# SPEAR_Speedy.net
KiCad netlist of a schematic drawn in EAGLE
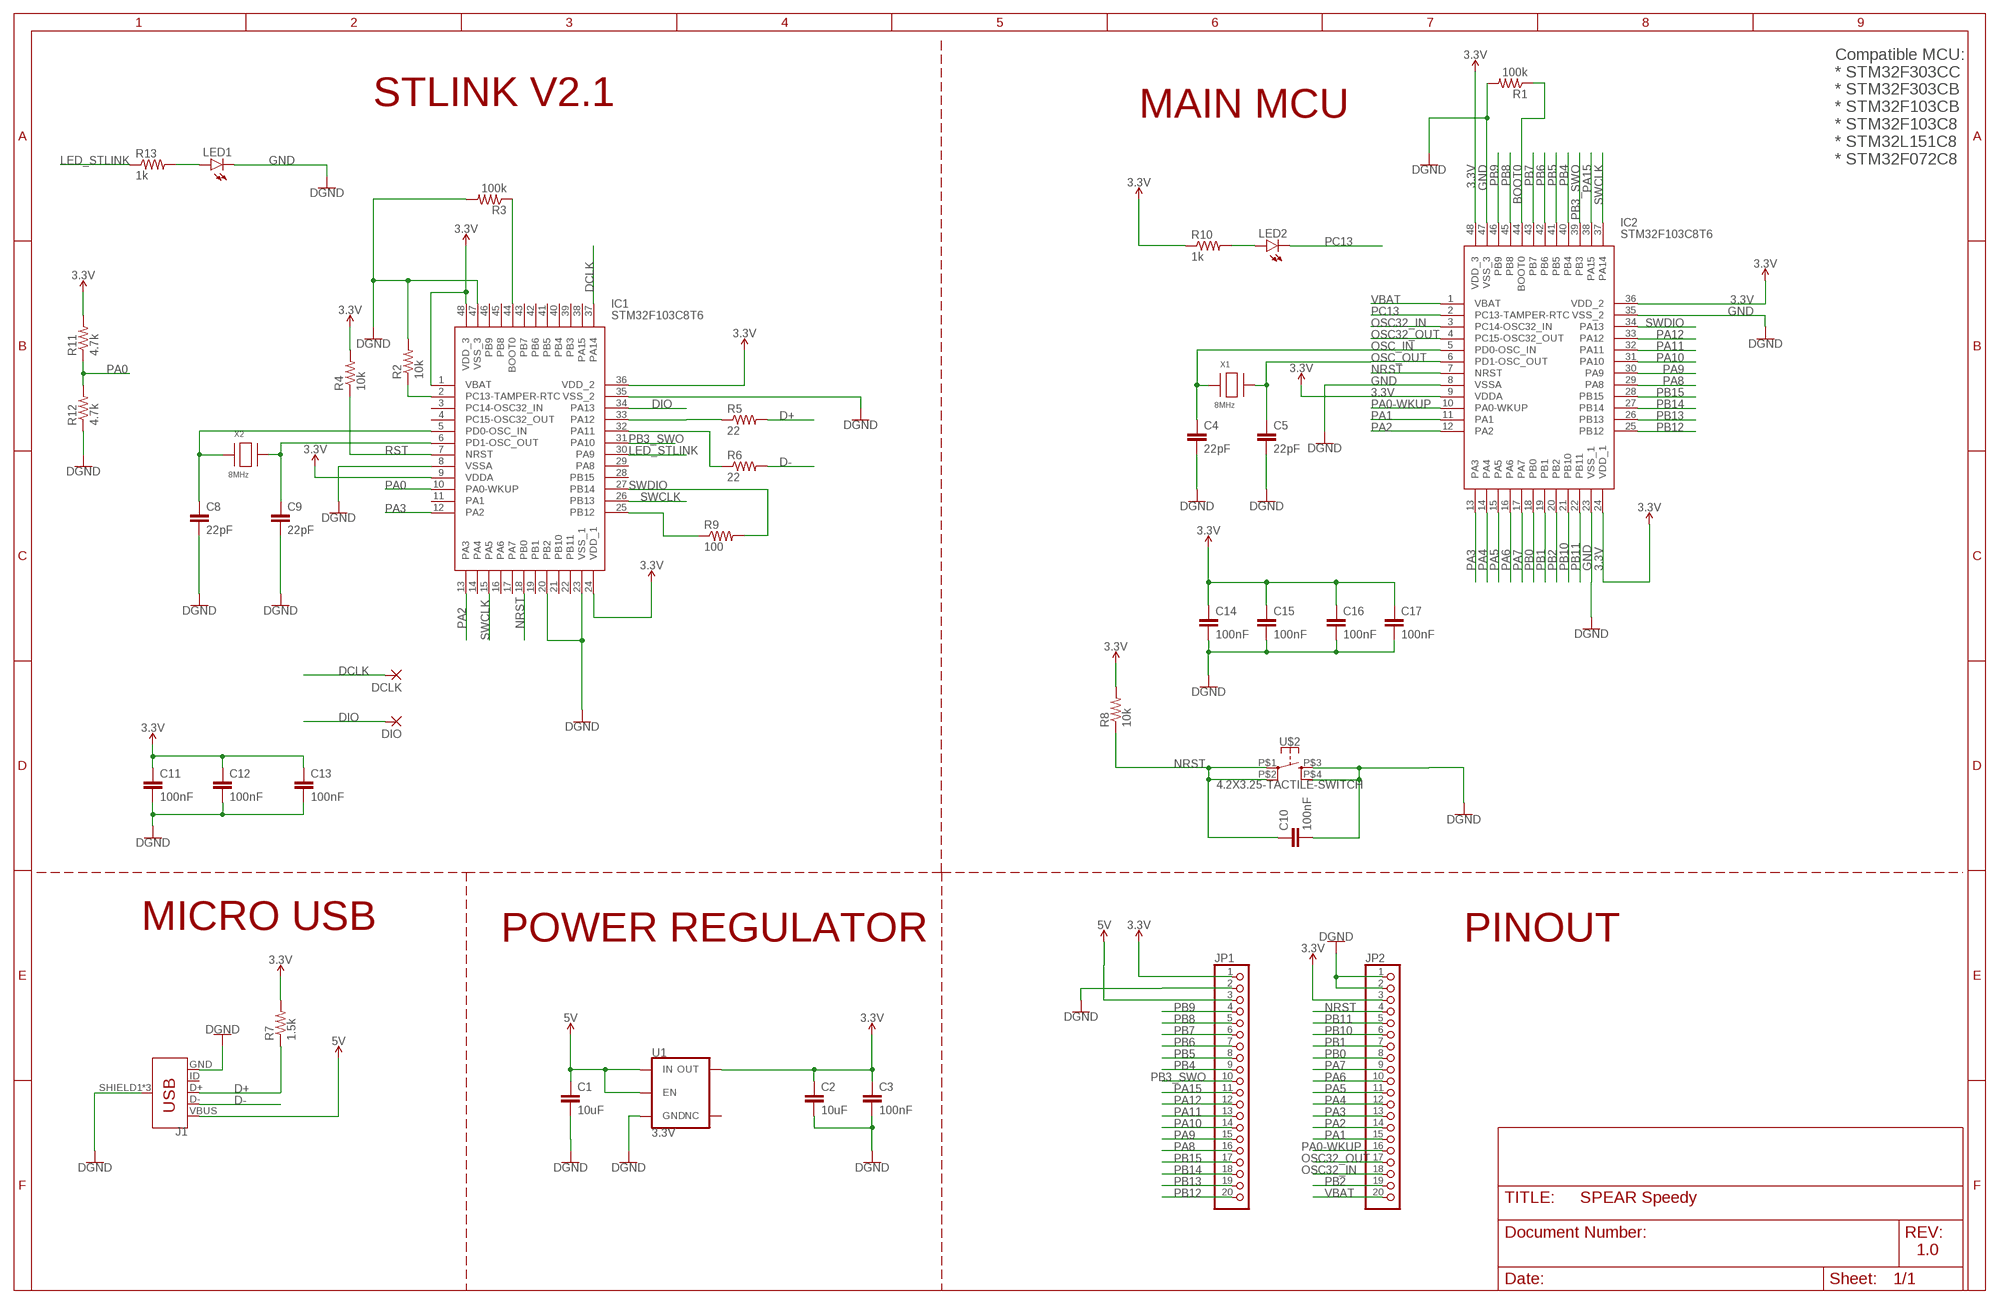
[diagram p0: schematic, sheet 1]

(export (version "E")
  (design (tool "Eeschema 10.0.6"))
  (components
    (comp (ref "C1")
      (value "10uF")
      (footprint "eagle-import:C0805")
      (libsource (lib "eagle-import") (part "C-EUC0805"))
    )
    (comp (ref "C2")
      (value "10uF")
      (footprint "eagle-import:C0805")
      (libsource (lib "eagle-import") (part "C-EUC0805"))
    )
    (comp (ref "C3")
      (value "100nF")
      (footprint "eagle-import:C0603")
      (libsource (lib "eagle-import") (part "C-EUC0603"))
    )
    (comp (ref "C4")
      (value "22pF")
      (footprint "eagle-import:C0603")
      (libsource (lib "eagle-import") (part "resistor_348_C-EUC0603"))
    )
    (comp (ref "C5")
      (value "22pF")
      (footprint "eagle-import:C0603")
      (libsource (lib "eagle-import") (part "resistor_348_C-EUC0603"))
    )
    (comp (ref "C8")
      (value "22pF")
      (footprint "eagle-import:C0603")
      (libsource (lib "eagle-import") (part "resistor_348_C-EUC0603"))
    )
    (comp (ref "C9")
      (value "22pF")
      (footprint "eagle-import:C0603")
      (libsource (lib "eagle-import") (part "resistor_348_C-EUC0603"))
    )
    (comp (ref "C10")
      (value "100nF")
      (footprint "eagle-import:C0603")
      (libsource (lib "eagle-import") (part "C-EUC0603"))
    )
    (comp (ref "C11")
      (value "100nF")
      (footprint "eagle-import:C0603")
      (libsource (lib "eagle-import") (part "C-EUC0603"))
    )
    (comp (ref "C12")
      (value "100nF")
      (footprint "eagle-import:C0603")
      (libsource (lib "eagle-import") (part "C-EUC0603"))
    )
    (comp (ref "C13")
      (value "100nF")
      (footprint "eagle-import:C0603")
      (libsource (lib "eagle-import") (part "C-EUC0603"))
    )
    (comp (ref "C14")
      (value "100nF")
      (footprint "eagle-import:C0603")
      (libsource (lib "eagle-import") (part "C-EUC0603"))
    )
    (comp (ref "C15")
      (value "100nF")
      (footprint "eagle-import:C0603")
      (libsource (lib "eagle-import") (part "C-EUC0603"))
    )
    (comp (ref "C16")
      (value "100nF")
      (footprint "eagle-import:C0603")
      (libsource (lib "eagle-import") (part "C-EUC0603"))
    )
    (comp (ref "C17")
      (value "100nF")
      (footprint "eagle-import:C0603")
      (libsource (lib "eagle-import") (part "C-EUC0603"))
    )
    (comp (ref "DCLK")
      (value "SMD2")
      (footprint "eagle-import:SMD1,27-2,54")
      (libsource (lib "eagle-import") (part "SMD2"))
    )
    (comp (ref "DIO")
      (value "SMD2")
      (footprint "eagle-import:SMD1,27-2,54")
      (libsource (lib "eagle-import") (part "SMD2"))
    )
    (comp (ref "IC1")
      (value "STM32F103C8T6")
      (footprint "eagle-import:QFP50P900X900X160-48N")
      (fields (field (name "MOUSER_PART_NUMBER") "511-STM32F103C8T6"))
      (libsource (lib "eagle-import") (part "STM32F103C8T6"))
    )
    (comp (ref "IC2")
      (value "STM32F103C8T6")
      (footprint "eagle-import:QFP50P900X900X160-48N")
      (fields (field (name "MOUSER_PART_NUMBER") "511-STM32F103C8T6"))
      (libsource (lib "eagle-import") (part "STM32F103C8T6"))
    )
    (comp (ref "J1")
      (value "USB_MICRO-B_FEMALE-SMT")
      (footprint "eagle-import:USB-B-MICRO-SMD")
      (libsource (lib "eagle-import") (part "USB_MICRO-B_FEMALE-SMT"))
    )
    (comp (ref "JP1")
      (value "PINHD-1X20")
      (footprint "eagle-import:1X20")
      (libsource (lib "eagle-import") (part "PINHD-1X20"))
    )
    (comp (ref "JP2")
      (value "PINHD-1X20")
      (footprint "eagle-import:1X20")
      (libsource (lib "eagle-import") (part "PINHD-1X20"))
    )
    (comp (ref "LED1")
      (value "LEDCHIP-LED0805")
      (footprint "eagle-import:CHIP-LED0805")
      (libsource (lib "eagle-import") (part "LEDCHIP-LED0805"))
    )
    (comp (ref "LED2")
      (value "LEDCHIP-LED0805")
      (footprint "eagle-import:CHIP-LED0805")
      (libsource (lib "eagle-import") (part "LEDCHIP-LED0805"))
    )
    (comp (ref "R1")
      (value "100k")
      (footprint "eagle-import:R0603")
      (libsource (lib "eagle-import") (part "R-US_R0603"))
    )
    (comp (ref "R2")
      (value "10k")
      (footprint "eagle-import:R0603")
      (libsource (lib "eagle-import") (part "R-US_R0603"))
    )
    (comp (ref "R3")
      (value "100k")
      (footprint "eagle-import:R0603")
      (libsource (lib "eagle-import") (part "R-US_R0603"))
    )
    (comp (ref "R4")
      (value "10k")
      (footprint "eagle-import:R0603")
      (libsource (lib "eagle-import") (part "R-US_R0603"))
    )
    (comp (ref "R5")
      (value "22")
      (footprint "eagle-import:R0603")
      (libsource (lib "eagle-import") (part "resistor_348_R-US_R0603"))
    )
    (comp (ref "R6")
      (value "22")
      (footprint "eagle-import:R0603")
      (libsource (lib "eagle-import") (part "resistor_348_R-US_R0603"))
    )
    (comp (ref "R7")
      (value "1.5k")
      (footprint "eagle-import:R0603")
      (libsource (lib "eagle-import") (part "resistor_348_R-US_R0603"))
    )
    (comp (ref "R8")
      (value "10k")
      (footprint "eagle-import:R0603")
      (libsource (lib "eagle-import") (part "R-US_R0603"))
    )
    (comp (ref "R9")
      (value "100")
      (footprint "eagle-import:R0603")
      (libsource (lib "eagle-import") (part "R-US_R0603"))
    )
    (comp (ref "R10")
      (value "1k")
      (footprint "eagle-import:R0603")
      (libsource (lib "eagle-import") (part "R-US_R0603"))
    )
    (comp (ref "R11")
      (value "4.7k")
      (footprint "eagle-import:R0603")
      (libsource (lib "eagle-import") (part "R-US_R0603"))
    )
    (comp (ref "R12")
      (value "4.7k")
      (footprint "eagle-import:R0603")
      (libsource (lib "eagle-import") (part "R-US_R0603"))
    )
    (comp (ref "R13")
      (value "1k")
      (footprint "eagle-import:R0603")
      (libsource (lib "eagle-import") (part "R-US_R0603"))
    )
    (comp (ref "U$2")
      (value "4.2X3.25-TACTILE-SWITCH")
      (footprint "eagle-import:4.2X3.25")
      (libsource (lib "eagle-import") (part "4.2X3.25-TACTILE-SWITCH"))
    )
    (comp (ref "U1")
      (value "3.3V")
      (footprint "eagle-import:SOT23-5")
      (libsource (lib "eagle-import") (part "V_REG_AP2112K-3.3V"))
    )
    (comp (ref "X1")
      (value "8MHz")
      (footprint "eagle-import:NX5032")
      (libsource (lib "eagle-import") (part "XTALNX5032"))
    )
    (comp (ref "X2")
      (value "8MHz")
      (footprint "eagle-import:NX5032")
      (libsource (lib "eagle-import") (part "XTALNX5032"))
    )
  )
  (nets
    (net (code "1") (name "/BOOT0") (class "Default")
      (node (ref "IC2") (pin "44") (pinfunction "BOOT0_44") (pintype "bidirectional"))
      (node (ref "R1") (pin "1") (pinfunction "1_1") (pintype "passive"))
    )
    (net (code "2") (name "/D+") (class "Default")
      (node (ref "J1") (pin "D+") (pinfunction "D+_D+") (pintype "bidirectional"))
      (node (ref "R5") (pin "2") (pinfunction "2_2") (pintype "passive"))
      (node (ref "R7") (pin "1") (pinfunction "1_1") (pintype "passive"))
    )
    (net (code "3") (name "/D-") (class "Default")
      (node (ref "J1") (pin "D-") (pinfunction "D-_D-") (pintype "bidirectional"))
      (node (ref "R6") (pin "2") (pinfunction "2_2") (pintype "passive"))
    )
    (net (code "4") (name "/DCLK") (class "Default")
      (node (ref "DCLK") (pin "1") (pinfunction "P_1") (pintype "passive"))
      (node (ref "IC1") (pin "37") (pinfunction "PA14_37") (pintype "bidirectional"))
    )
    (net (code "5") (name "/DIO") (class "Default")
      (node (ref "DIO") (pin "1") (pinfunction "P_1") (pintype "passive"))
      (node (ref "IC1") (pin "34") (pinfunction "PA13_34") (pintype "bidirectional"))
    )
    (net (code "6") (name "/LED_STLINK") (class "Default")
      (node (ref "IC1") (pin "30") (pinfunction "PA9_30") (pintype "bidirectional"))
      (node (ref "R13") (pin "1") (pinfunction "1_1") (pintype "passive"))
    )
    (net (code "7") (name "/NRST") (class "Default")
      (node (ref "C10") (pin "1") (pinfunction "1_1") (pintype "passive"))
      (node (ref "IC1") (pin "18") (pinfunction "PB0_18") (pintype "bidirectional"))
      (node (ref "IC2") (pin "7") (pinfunction "NRST_7") (pintype "input"))
      (node (ref "JP2") (pin "4") (pinfunction "4_4") (pintype "passive"))
      (node (ref "R8") (pin "1") (pinfunction "1_1") (pintype "passive"))
      (node (ref "U$2") (pin "P$1") (pinfunction "1_P$1") (pintype "passive"))
      (node (ref "U$2") (pin "P$2") (pinfunction "2_P$2") (pintype "passive"))
    )
    (net (code "8") (name "/OSC32_IN") (class "Default")
      (node (ref "IC2") (pin "3") (pinfunction "PC14-OSC32_IN_3") (pintype "input"))
      (node (ref "JP2") (pin "18") (pinfunction "18_18") (pintype "passive"))
    )
    (net (code "9") (name "/OSC32_OUT") (class "Default")
      (node (ref "IC2") (pin "4") (pinfunction "PC15-OSC32_OUT_4") (pintype "output"))
      (node (ref "JP2") (pin "17") (pinfunction "17_17") (pintype "passive"))
    )
    (net (code "10") (name "/OSC_IN") (class "Default")
      (node (ref "C4") (pin "1") (pinfunction "1_1") (pintype "passive"))
      (node (ref "IC2") (pin "5") (pinfunction "PD0-OSC_IN_5") (pintype "input"))
      (node (ref "X1") (pin "P$1") (pinfunction "P$1_P$1") (pintype "bidirectional"))
    )
    (net (code "11") (name "/OSC_OUT") (class "Default")
      (node (ref "C5") (pin "1") (pinfunction "1_1") (pintype "passive"))
      (node (ref "IC2") (pin "6") (pinfunction "PD1-OSC_OUT_6") (pintype "output"))
      (node (ref "X1") (pin "P$2") (pinfunction "P$2_P$2") (pintype "bidirectional"))
    )
    (net (code "12") (name "/PA0") (class "Default")
      (node (ref "IC1") (pin "10") (pinfunction "PA0-WKUP_10") (pintype "bidirectional"))
      (node (ref "R11") (pin "1") (pinfunction "1_1") (pintype "passive"))
      (node (ref "R12") (pin "2") (pinfunction "2_2") (pintype "passive"))
    )
    (net (code "13") (name "/PA0-WKUP") (class "Default")
      (node (ref "IC2") (pin "10") (pinfunction "PA0-WKUP_10") (pintype "bidirectional"))
      (node (ref "JP2") (pin "16") (pinfunction "16_16") (pintype "passive"))
    )
    (net (code "14") (name "/PA1") (class "Default")
      (node (ref "IC2") (pin "11") (pinfunction "PA1_11") (pintype "bidirectional"))
      (node (ref "JP2") (pin "15") (pinfunction "15_15") (pintype "passive"))
    )
    (net (code "15") (name "/PA2") (class "Default")
      (node (ref "IC1") (pin "13") (pinfunction "PA3_13") (pintype "bidirectional"))
      (node (ref "IC2") (pin "12") (pinfunction "PA2_12") (pintype "bidirectional"))
      (node (ref "JP2") (pin "14") (pinfunction "14_14") (pintype "passive"))
    )
    (net (code "16") (name "/PA3") (class "Default")
      (node (ref "IC1") (pin "12") (pinfunction "PA2_12") (pintype "bidirectional"))
      (node (ref "IC2") (pin "13") (pinfunction "PA3_13") (pintype "bidirectional"))
      (node (ref "JP2") (pin "13") (pinfunction "13_13") (pintype "passive"))
    )
    (net (code "17") (name "/PA4") (class "Default")
      (node (ref "IC2") (pin "14") (pinfunction "PA4_14") (pintype "bidirectional"))
      (node (ref "JP2") (pin "12") (pinfunction "12_12") (pintype "passive"))
    )
    (net (code "18") (name "/PA5") (class "Default")
      (node (ref "IC2") (pin "15") (pinfunction "PA5_15") (pintype "bidirectional"))
      (node (ref "JP2") (pin "11") (pinfunction "11_11") (pintype "passive"))
    )
    (net (code "19") (name "/PA6") (class "Default")
      (node (ref "IC2") (pin "16") (pinfunction "PA6_16") (pintype "bidirectional"))
      (node (ref "JP2") (pin "10") (pinfunction "10_10") (pintype "passive"))
    )
    (net (code "20") (name "/PA7") (class "Default")
      (node (ref "IC2") (pin "17") (pinfunction "PA7_17") (pintype "bidirectional"))
      (node (ref "JP2") (pin "9") (pinfunction "9_9") (pintype "passive"))
    )
    (net (code "21") (name "/PA8") (class "Default")
      (node (ref "IC2") (pin "29") (pinfunction "PA8_29") (pintype "bidirectional"))
      (node (ref "JP1") (pin "16") (pinfunction "16_16") (pintype "passive"))
    )
    (net (code "22") (name "/PA9") (class "Default")
      (node (ref "IC2") (pin "30") (pinfunction "PA9_30") (pintype "bidirectional"))
      (node (ref "JP1") (pin "15") (pinfunction "15_15") (pintype "passive"))
    )
    (net (code "23") (name "/PA10") (class "Default")
      (node (ref "IC2") (pin "31") (pinfunction "PA10_31") (pintype "bidirectional"))
      (node (ref "JP1") (pin "14") (pinfunction "14_14") (pintype "passive"))
    )
    (net (code "24") (name "/PA11") (class "Default")
      (node (ref "IC2") (pin "32") (pinfunction "PA11_32") (pintype "bidirectional"))
      (node (ref "JP1") (pin "13") (pinfunction "13_13") (pintype "passive"))
    )
    (net (code "25") (name "/PA12") (class "Default")
      (node (ref "IC2") (pin "33") (pinfunction "PA12_33") (pintype "bidirectional"))
      (node (ref "JP1") (pin "12") (pinfunction "12_12") (pintype "passive"))
    )
    (net (code "26") (name "/PA15") (class "Default")
      (node (ref "IC2") (pin "38") (pinfunction "PA15_38") (pintype "bidirectional"))
      (node (ref "JP1") (pin "11") (pinfunction "11_11") (pintype "passive"))
    )
    (net (code "27") (name "/PB0") (class "Default")
      (node (ref "IC2") (pin "18") (pinfunction "PB0_18") (pintype "bidirectional"))
      (node (ref "JP2") (pin "8") (pinfunction "8_8") (pintype "passive"))
    )
    (net (code "28") (name "/PB1") (class "Default")
      (node (ref "IC2") (pin "19") (pinfunction "PB1_19") (pintype "bidirectional"))
      (node (ref "JP2") (pin "7") (pinfunction "7_7") (pintype "passive"))
    )
    (net (code "29") (name "/PB2") (class "Default")
      (node (ref "IC2") (pin "20") (pinfunction "PB2_20") (pintype "bidirectional"))
      (node (ref "JP2") (pin "19") (pinfunction "19_19") (pintype "passive"))
    )
    (net (code "30") (name "/PB3_SWO") (class "Default")
      (node (ref "IC1") (pin "31") (pinfunction "PA10_31") (pintype "bidirectional"))
      (node (ref "IC2") (pin "39") (pinfunction "PB3_39") (pintype "bidirectional"))
      (node (ref "JP1") (pin "10") (pinfunction "10_10") (pintype "passive"))
    )
    (net (code "31") (name "/PB4") (class "Default")
      (node (ref "IC2") (pin "40") (pinfunction "PB4_40") (pintype "bidirectional"))
      (node (ref "JP1") (pin "9") (pinfunction "9_9") (pintype "passive"))
    )
    (net (code "32") (name "/PB5") (class "Default")
      (node (ref "IC2") (pin "41") (pinfunction "PB5_41") (pintype "bidirectional"))
      (node (ref "JP1") (pin "8") (pinfunction "8_8") (pintype "passive"))
    )
    (net (code "33") (name "/PB6") (class "Default")
      (node (ref "IC2") (pin "42") (pinfunction "PB6_42") (pintype "bidirectional"))
      (node (ref "JP1") (pin "7") (pinfunction "7_7") (pintype "passive"))
    )
    (net (code "34") (name "/PB7") (class "Default")
      (node (ref "IC2") (pin "43") (pinfunction "PB7_43") (pintype "bidirectional"))
      (node (ref "JP1") (pin "6") (pinfunction "6_6") (pintype "passive"))
    )
    (net (code "35") (name "/PB8") (class "Default")
      (node (ref "IC2") (pin "45") (pinfunction "PB8_45") (pintype "bidirectional"))
      (node (ref "JP1") (pin "5") (pinfunction "5_5") (pintype "passive"))
    )
    (net (code "36") (name "/PB9") (class "Default")
      (node (ref "IC2") (pin "46") (pinfunction "PB9_46") (pintype "bidirectional"))
      (node (ref "JP1") (pin "4") (pinfunction "4_4") (pintype "passive"))
    )
    (net (code "37") (name "/PB10") (class "Default")
      (node (ref "IC2") (pin "21") (pinfunction "PB10_21") (pintype "bidirectional"))
      (node (ref "JP2") (pin "6") (pinfunction "6_6") (pintype "passive"))
    )
    (net (code "38") (name "/PB11") (class "Default")
      (node (ref "IC2") (pin "22") (pinfunction "PB11_22") (pintype "bidirectional"))
      (node (ref "JP2") (pin "5") (pinfunction "5_5") (pintype "passive"))
    )
    (net (code "39") (name "/PB12") (class "Default")
      (node (ref "IC2") (pin "25") (pinfunction "PB12_25") (pintype "bidirectional"))
      (node (ref "JP1") (pin "20") (pinfunction "20_20") (pintype "passive"))
    )
    (net (code "40") (name "/PB13") (class "Default")
      (node (ref "IC2") (pin "26") (pinfunction "PB13_26") (pintype "bidirectional"))
      (node (ref "JP1") (pin "19") (pinfunction "19_19") (pintype "passive"))
    )
    (net (code "41") (name "/PB14") (class "Default")
      (node (ref "IC2") (pin "27") (pinfunction "PB14_27") (pintype "bidirectional"))
      (node (ref "JP1") (pin "18") (pinfunction "18_18") (pintype "passive"))
    )
    (net (code "42") (name "/PB15") (class "Default")
      (node (ref "IC2") (pin "28") (pinfunction "PB15_28") (pintype "bidirectional"))
      (node (ref "JP1") (pin "17") (pinfunction "17_17") (pintype "passive"))
    )
    (net (code "43") (name "/PC13") (class "Default")
      (node (ref "IC2") (pin "2") (pinfunction "PC13-TAMPER-RTC_2") (pintype "bidirectional"))
      (node (ref "LED2") (pin "C") (pinfunction "C_C") (pintype "passive"))
    )
    (net (code "44") (name "/RST") (class "Default")
      (node (ref "IC1") (pin "7") (pinfunction "NRST_7") (pintype "input"))
      (node (ref "R4") (pin "1") (pinfunction "1_1") (pintype "passive"))
    )
    (net (code "45") (name "/SWCLK") (class "Default")
      (node (ref "IC1") (pin "15") (pinfunction "PA5_15") (pintype "bidirectional"))
      (node (ref "IC1") (pin "26") (pinfunction "PB13_26") (pintype "bidirectional"))
      (node (ref "IC2") (pin "37") (pinfunction "PA14_37") (pintype "bidirectional"))
    )
    (net (code "46") (name "/SWDIO") (class "Default")
      (node (ref "IC1") (pin "27") (pinfunction "PB14_27") (pintype "bidirectional"))
      (node (ref "IC2") (pin "34") (pinfunction "PA13_34") (pintype "bidirectional"))
      (node (ref "R9") (pin "2") (pinfunction "2_2") (pintype "passive"))
    )
    (net (code "47") (name "/VBAT") (class "Default")
      (node (ref "IC2") (pin "1") (pinfunction "VBAT_1") (pintype "bidirectional"))
      (node (ref "JP2") (pin "20") (pinfunction "20_20") (pintype "passive"))
    )
    (net (code "48") (name "3.3V") (class "Default")
      (node (ref "C11") (pin "1") (pinfunction "1_1") (pintype "passive"))
      (node (ref "C12") (pin "1") (pinfunction "1_1") (pintype "passive"))
      (node (ref "C13") (pin "1") (pinfunction "1_1") (pintype "passive"))
      (node (ref "C14") (pin "1") (pinfunction "1_1") (pintype "passive"))
      (node (ref "C15") (pin "1") (pinfunction "1_1") (pintype "passive"))
      (node (ref "C16") (pin "1") (pinfunction "1_1") (pintype "passive"))
      (node (ref "C17") (pin "1") (pinfunction "1_1") (pintype "passive"))
      (node (ref "C2") (pin "1") (pinfunction "1_1") (pintype "passive"))
      (node (ref "C3") (pin "1") (pinfunction "1_1") (pintype "passive"))
      (node (ref "IC1") (pin "1") (pinfunction "VBAT_1") (pintype "bidirectional"))
      (node (ref "IC1") (pin "24") (pinfunction "VDD_1_24") (pintype "power_in"))
      (node (ref "IC1") (pin "36") (pinfunction "VDD_2_36") (pintype "power_in"))
      (node (ref "IC1") (pin "48") (pinfunction "VDD_3_48") (pintype "power_in"))
      (node (ref "IC1") (pin "9") (pinfunction "VDDA_9") (pintype "power_in"))
      (node (ref "IC2") (pin "24") (pinfunction "VDD_1_24") (pintype "power_in"))
      (node (ref "IC2") (pin "36") (pinfunction "VDD_2_36") (pintype "power_in"))
      (node (ref "IC2") (pin "48") (pinfunction "VDD_3_48") (pintype "power_in"))
      (node (ref "IC2") (pin "9") (pinfunction "VDDA_9") (pintype "power_in"))
      (node (ref "JP1") (pin "1") (pinfunction "1_1") (pintype "passive"))
      (node (ref "JP2") (pin "3") (pinfunction "3_3") (pintype "passive"))
      (node (ref "R10") (pin "1") (pinfunction "1_1") (pintype "passive"))
      (node (ref "R11") (pin "2") (pinfunction "2_2") (pintype "passive"))
      (node (ref "R4") (pin "2") (pinfunction "2_2") (pintype "passive"))
      (node (ref "R7") (pin "2") (pinfunction "2_2") (pintype "passive"))
      (node (ref "R8") (pin "2") (pinfunction "2_2") (pintype "passive"))
      (node (ref "U1") (pin "5") (pinfunction "OUT_5") (pintype "passive"))
    )
    (net (code "49") (name "5V") (class "Default")
      (node (ref "C1") (pin "1") (pinfunction "1_1") (pintype "passive"))
      (node (ref "J1") (pin "VBUS") (pinfunction "VBUS_VBUS") (pintype "power_in"))
      (node (ref "JP1") (pin "3") (pinfunction "3_3") (pintype "passive"))
      (node (ref "U1") (pin "1") (pinfunction "IN_1") (pintype "input"))
      (node (ref "U1") (pin "3") (pinfunction "EN_3") (pintype "input"))
    )
    (net (code "50") (name "DGND") (class "Default")
      (node (ref "C1") (pin "2") (pinfunction "2_2") (pintype "passive"))
      (node (ref "C10") (pin "2") (pinfunction "2_2") (pintype "passive"))
      (node (ref "C11") (pin "2") (pinfunction "2_2") (pintype "passive"))
      (node (ref "C12") (pin "2") (pinfunction "2_2") (pintype "passive"))
      (node (ref "C13") (pin "2") (pinfunction "2_2") (pintype "passive"))
      (node (ref "C14") (pin "2") (pinfunction "2_2") (pintype "passive"))
      (node (ref "C15") (pin "2") (pinfunction "2_2") (pintype "passive"))
      (node (ref "C16") (pin "2") (pinfunction "2_2") (pintype "passive"))
      (node (ref "C17") (pin "2") (pinfunction "2_2") (pintype "passive"))
      (node (ref "C2") (pin "2") (pinfunction "2_2") (pintype "passive"))
      (node (ref "C3") (pin "2") (pinfunction "2_2") (pintype "passive"))
      (node (ref "C4") (pin "2") (pinfunction "2_2") (pintype "passive"))
      (node (ref "C5") (pin "2") (pinfunction "2_2") (pintype "passive"))
      (node (ref "C8") (pin "2") (pinfunction "2_2") (pintype "passive"))
      (node (ref "C9") (pin "2") (pinfunction "2_2") (pintype "passive"))
      (node (ref "IC1") (pin "20") (pinfunction "PB2_20") (pintype "bidirectional"))
      (node (ref "IC1") (pin "23") (pinfunction "VSS_1_23") (pintype "power_in"))
      (node (ref "IC1") (pin "35") (pinfunction "VSS_2_35") (pintype "power_in"))
      (node (ref "IC1") (pin "47") (pinfunction "VSS_3_47") (pintype "power_in"))
      (node (ref "IC1") (pin "8") (pinfunction "VSSA_8") (pintype "power_in"))
      (node (ref "IC2") (pin "23") (pinfunction "VSS_1_23") (pintype "power_in"))
      (node (ref "IC2") (pin "35") (pinfunction "VSS_2_35") (pintype "power_in"))
      (node (ref "IC2") (pin "47") (pinfunction "VSS_3_47") (pintype "power_in"))
      (node (ref "IC2") (pin "8") (pinfunction "VSSA_8") (pintype "power_in"))
      (node (ref "J1") (pin "GND") (pinfunction "GND_GND") (pintype "power_in"))
      (node (ref "J1") (pin "SHIELD1") (pinfunction "SHIELD_SHIELD1") (pintype "bidirectional"))
      (node (ref "J1") (pin "SHIELD2") (pinfunction "SHIELD_SHIELD2") (pintype "bidirectional"))
      (node (ref "J1") (pin "SHIELD3") (pinfunction "SHIELD_SHIELD3") (pintype "bidirectional"))
      (node (ref "JP1") (pin "2") (pinfunction "2_2") (pintype "passive"))
      (node (ref "JP2") (pin "1") (pinfunction "1_1") (pintype "passive"))
      (node (ref "JP2") (pin "2") (pinfunction "2_2") (pintype "passive"))
      (node (ref "LED1") (pin "C") (pinfunction "C_C") (pintype "passive"))
      (node (ref "R1") (pin "2") (pinfunction "2_2") (pintype "passive"))
      (node (ref "R12") (pin "1") (pinfunction "1_1") (pintype "passive"))
      (node (ref "R2") (pin "2") (pinfunction "2_2") (pintype "passive"))
      (node (ref "R3") (pin "2") (pinfunction "2_2") (pintype "passive"))
      (node (ref "U$2") (pin "P$3") (pinfunction "3_P$3") (pintype "passive"))
      (node (ref "U$2") (pin "P$4") (pinfunction "4_P$4") (pintype "passive"))
      (node (ref "U1") (pin "2") (pinfunction "GND_2") (pintype "input"))
    )
    (net (code "51") (name "Net-(IC1-BOOT0)") (class "Default")
      (node (ref "IC1") (pin "44") (pinfunction "BOOT0_44") (pintype "bidirectional"))
      (node (ref "R3") (pin "1") (pinfunction "1_1") (pintype "passive"))
    )
    (net (code "52") (name "Net-(IC1-PA11)") (class "Default")
      (node (ref "IC1") (pin "32") (pinfunction "PA11_32") (pintype "bidirectional"))
      (node (ref "R6") (pin "1") (pinfunction "1_1") (pintype "passive"))
    )
    (net (code "53") (name "Net-(IC1-PA12)") (class "Default")
      (node (ref "IC1") (pin "33") (pinfunction "PA12_33") (pintype "bidirectional"))
      (node (ref "R5") (pin "1") (pinfunction "1_1") (pintype "passive"))
    )
    (net (code "54") (name "Net-(IC1-PB12)") (class "Default")
      (node (ref "IC1") (pin "25") (pinfunction "PB12_25") (pintype "bidirectional"))
      (node (ref "R9") (pin "1") (pinfunction "1_1") (pintype "passive"))
    )
    (net (code "55") (name "Net-(IC1-PC13-TAMPER-RTC)") (class "Default")
      (node (ref "IC1") (pin "2") (pinfunction "PC13-TAMPER-RTC_2") (pintype "bidirectional"))
      (node (ref "R2") (pin "1") (pinfunction "1_1") (pintype "passive"))
    )
    (net (code "56") (name "Net-(IC1-PD0-OSC_IN)") (class "Default")
      (node (ref "C8") (pin "1") (pinfunction "1_1") (pintype "passive"))
      (node (ref "IC1") (pin "5") (pinfunction "PD0-OSC_IN_5") (pintype "input"))
      (node (ref "X2") (pin "P$1") (pinfunction "P$1_P$1") (pintype "bidirectional"))
    )
    (net (code "57") (name "Net-(IC1-PD1-OSC_OUT)") (class "Default")
      (node (ref "C9") (pin "1") (pinfunction "1_1") (pintype "passive"))
      (node (ref "IC1") (pin "6") (pinfunction "PD1-OSC_OUT_6") (pintype "output"))
      (node (ref "X2") (pin "P$2") (pinfunction "P$2_P$2") (pintype "bidirectional"))
    )
    (net (code "58") (name "Net-(LED1-PadA)") (class "Default")
      (node (ref "LED1") (pin "A") (pinfunction "A_A") (pintype "passive"))
      (node (ref "R13") (pin "2") (pinfunction "2_2") (pintype "passive"))
    )
    (net (code "59") (name "Net-(LED2-PadA)") (class "Default")
      (node (ref "LED2") (pin "A") (pinfunction "A_A") (pintype "passive"))
      (node (ref "R10") (pin "2") (pinfunction "2_2") (pintype "passive"))
    )
    (net (code "60") (name "unconnected-(IC1-PA1-Pad11)") (class "Default")
      (node (ref "IC1") (pin "11") (pinfunction "PA1_11") (pintype "bidirectional"))
    )
    (net (code "61") (name "unconnected-(IC1-PA4-Pad14)") (class "Default")
      (node (ref "IC1") (pin "14") (pinfunction "PA4_14") (pintype "bidirectional"))
    )
    (net (code "62") (name "unconnected-(IC1-PA6-Pad16)") (class "Default")
      (node (ref "IC1") (pin "16") (pinfunction "PA6_16") (pintype "bidirectional"))
    )
    (net (code "63") (name "unconnected-(IC1-PA7-Pad17)") (class "Default")
      (node (ref "IC1") (pin "17") (pinfunction "PA7_17") (pintype "bidirectional"))
    )
    (net (code "64") (name "unconnected-(IC1-PA8-Pad29)") (class "Default")
      (node (ref "IC1") (pin "29") (pinfunction "PA8_29") (pintype "bidirectional"))
    )
    (net (code "65") (name "unconnected-(IC1-PA15-Pad38)") (class "Default")
      (node (ref "IC1") (pin "38") (pinfunction "PA15_38") (pintype "bidirectional"))
    )
    (net (code "66") (name "unconnected-(IC1-PB1-Pad19)") (class "Default")
      (node (ref "IC1") (pin "19") (pinfunction "PB1_19") (pintype "bidirectional"))
    )
    (net (code "67") (name "unconnected-(IC1-PB3-Pad39)") (class "Default")
      (node (ref "IC1") (pin "39") (pinfunction "PB3_39") (pintype "bidirectional"))
    )
    (net (code "68") (name "unconnected-(IC1-PB4-Pad40)") (class "Default")
      (node (ref "IC1") (pin "40") (pinfunction "PB4_40") (pintype "bidirectional"))
    )
    (net (code "69") (name "unconnected-(IC1-PB5-Pad41)") (class "Default")
      (node (ref "IC1") (pin "41") (pinfunction "PB5_41") (pintype "bidirectional"))
    )
    (net (code "70") (name "unconnected-(IC1-PB6-Pad42)") (class "Default")
      (node (ref "IC1") (pin "42") (pinfunction "PB6_42") (pintype "bidirectional"))
    )
    (net (code "71") (name "unconnected-(IC1-PB7-Pad43)") (class "Default")
      (node (ref "IC1") (pin "43") (pinfunction "PB7_43") (pintype "bidirectional"))
    )
    (net (code "72") (name "unconnected-(IC1-PB8-Pad45)") (class "Default")
      (node (ref "IC1") (pin "45") (pinfunction "PB8_45") (pintype "bidirectional"))
    )
    (net (code "73") (name "unconnected-(IC1-PB9-Pad46)") (class "Default")
      (node (ref "IC1") (pin "46") (pinfunction "PB9_46") (pintype "bidirectional"))
    )
    (net (code "74") (name "unconnected-(IC1-PB10-Pad21)") (class "Default")
      (node (ref "IC1") (pin "21") (pinfunction "PB10_21") (pintype "bidirectional"))
    )
    (net (code "75") (name "unconnected-(IC1-PB11-Pad22)") (class "Default")
      (node (ref "IC1") (pin "22") (pinfunction "PB11_22") (pintype "bidirectional"))
    )
    (net (code "76") (name "unconnected-(IC1-PB15-Pad28)") (class "Default")
      (node (ref "IC1") (pin "28") (pinfunction "PB15_28") (pintype "bidirectional"))
    )
    (net (code "77") (name "unconnected-(IC1-PC14-OSC32_IN-Pad3)") (class "Default")
      (node (ref "IC1") (pin "3") (pinfunction "PC14-OSC32_IN_3") (pintype "input"))
    )
    (net (code "78") (name "unconnected-(IC1-PC15-OSC32_OUT-Pad4)") (class "Default")
      (node (ref "IC1") (pin "4") (pinfunction "PC15-OSC32_OUT_4") (pintype "output"))
    )
    (net (code "79") (name "unconnected-(J1-PadID)") (class "Default")
      (node (ref "J1") (pin "ID") (pinfunction "ID_ID") (pintype "bidirectional"))
    )
    (net (code "80") (name "unconnected-(U1-NC-Pad4)") (class "Default")
      (node (ref "U1") (pin "4") (pinfunction "NC_4") (pintype "no_connect"))
    )
  )
)
